# NXP_USB_Programmer.net
KiCad netlist of a schematic drawn in Altium Designer
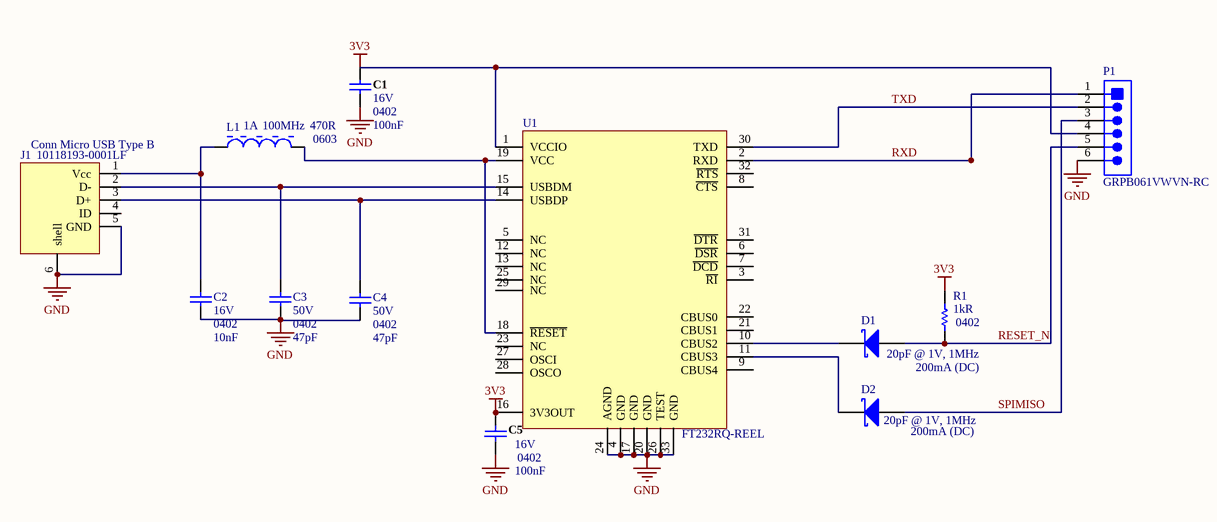
[diagram p0: NXP_USB_Programmer.SchDoc]

(export (version "E")
  (design (tool "Eeschema 10.0.6"))
  (components
    (comp (ref "C1")
      (value "CAP CER 0.1UF 16V X7R 0402")
      (footprint "PcbLib1:SM0402")
      (description "0.1µF ±10% 16V Ceramic Capacitor X7R 0402 (1005 Metric)")
      (fields
        (field (name "MANUFACTURER") "Yageo")
        (field (name "MANUFACTURER PART NUMBER") "CC0402KRX7R7BB104")
        (field (name "VOLTAGE RATING") "16V")
        (field (name "CASE/PACKAGE") "0402")
        (field (name "CAPACITANCE") "100nF")
      )
      (libsource (lib "") (part "CC0402KRX7R7BB104_1"))
    )
    (comp (ref "C2")
      (value "CAP CER 10000PF 16V X7R 0402")
      (footprint "PcbLib1:SM0402")
      (description "10000pF ±10% 16V Ceramic Capacitor X7R 0402 (1005 Metric)")
      (fields
        (field (name "TOLERANCE") "Â±10%")
        (field (name "MANUFACTURER") "KEMET")
        (field (name "VOLTAGE RATING") "16V")
        (field (name "CASE/PACKAGE") "0402")
        (field (name "CAPACITANCE") "10nF")
      )
      (libsource (lib "Schlib1") (part "C0402C103K4RALTU"))
    )
    (comp (ref "C3")
      (value "CAP CER 47PF 50V NP0 0402")
      (footprint "PcbLib1:SM0402")
      (description "47pF ±0.5pF 50V Ceramic Capacitor C0G, NP0 0402 (1005 Metric)")
      (fields
        (field (name "MANUFACTURER") "KEMET")
        (field (name "MANUFACTURER PART NUMBER") "C0402C470D5GACTU")
        (field (name "VOLTAGE RATING") "50V")
        (field (name "CASE/PACKAGE") "0402")
        (field (name "CAPACITANCE") "47pF")
      )
      (libsource (lib "Schlib1") (part "C0402C470D5GACTU"))
    )
    (comp (ref "C4")
      (value "CAP CER 47PF 50V NP0 0402")
      (footprint "PcbLib1:SM0402")
      (description "47pF ±0.5pF 50V Ceramic Capacitor C0G, NP0 0402 (1005 Metric)")
      (fields
        (field (name "MANUFACTURER") "KEMET")
        (field (name "MANUFACTURER PART NUMBER") "C0402C470D5GACTU")
        (field (name "VOLTAGE RATING") "50V")
        (field (name "CASE/PACKAGE") "0402")
        (field (name "CAPACITANCE") "47pF")
      )
      (libsource (lib "Schlib1") (part "C0402C470D5GACTU"))
    )
    (comp (ref "C5")
      (value "CAP CER 0.1UF 16V X7R 0402")
      (footprint "PcbLib1:SM0402")
      (description "0.1µF ±10% 16V Ceramic Capacitor X7R 0402 (1005 Metric)")
      (fields
        (field (name "MANUFACTURER") "Yageo")
        (field (name "MANUFACTURER PART NUMBER") "CC0402KRX7R7BB104")
        (field (name "VOLTAGE RATING") "16V")
        (field (name "CASE/PACKAGE") "0402")
        (field (name "CAPACITANCE") "100nF")
      )
      (libsource (lib "Schlib1") (part "CC0402KRX7R7BB104"))
    )
    (comp (ref "D1")
      (value "DIODE SCHOTTKY 30V 200MA SOD523")
      (footprint "PcbLib1:DIODE SOD523")
      (description "Schottky Barrier Diode, 30 V, 0.2 A, -55 to 125 degC, 2-Pin SOD523F, RoHS, Tape and Reel")
      (fields
        (field (name "MANUFACTURER PART NUMBER") "RB521S30,115")
        (field (name "MANUFACTURER") "Nexperia")
        (field (name "CAPACITANCE @ VR, F") "20pF @ 1V, 1MHz")
        (field (name "CURRENT - AVERAGE RECTIFIED (IO)") "200mA (DC)")
      )
      (libsource (lib "Schlib1") (part "RB521S30,115"))
    )
    (comp (ref "D2")
      (value "DIODE SCHOTTKY 30V 200MA SOD523")
      (footprint "PcbLib1:DIODE SOD523")
      (description "Schottky Barrier Diode, 30 V, 0.2 A, -55 to 125 degC, 2-Pin SOD523F, RoHS, Tape and Reel")
      (fields
        (field (name "MANUFACTURER PART NUMBER") "RB521S30,115")
        (field (name "MANUFACTURER") "Nexperia")
        (field (name "CAPACITANCE @ VR, F") "20pF @ 1V, 1MHz")
        (field (name "CURRENT - AVERAGE RECTIFIED (IO)") "200mA (DC)")
      )
      (libsource (lib "Schlib1") (part "RB521S30,115"))
    )
    (comp (ref "J1")
      (value "10118193-0001LF")
      (footprint "PcbLib1:FCI-10118193-0001LF-5_V")
      (description "USB - micro B USB 2.0 Receptacle Connector 5 Position Surface Mount, Right Angle; Through Hole")
      (fields
        (field (name "MANUFACTURER") "Amphenol ICC")
        (field (name "DESCRIPTION2") "Conn Micro USB Type B")
        (field (name "MANUFACTURER PART NUMBER") "10118193-0001LF")
      )
      (libsource (lib "Schlib1") (part "10118193-0001LF"))
    )
    (comp (ref "L1")
      (value "FERRITE BEAD 470 OHM 0603 1LN")
      (footprint "PcbLib1:BLM18PG471SN1D")
      (description "470 Ohms @ 100MHz 1 Power Line Ferrite Bead 0603 (1608 Metric) 1A 200mOhm")
      (fields
        (field (name "MANUFACTURER") "Murata")
        (field (name "MANUFACTURER PART NUMBER") "BLM18PG471SN1D")
        (field (name "MAX CURRENT RATING") "1A")
        (field (name "TEST FREQUENCY") "100MHz")
        (field (name "IMPEDANCE") "470R")
        (field (name "CASE/PACKAGE") "0603")
      )
      (libsource (lib "Schlib1") (part "BLM18PG471SN1D"))
    )
    (comp (ref "P1")
      (value "CONN HEADER VERT 6POS 1.27MM")
      (footprint "PcbLib1:SLIN-GRPB061VWVN-RC_V")
      (description "Connector Header Through Hole 6 position 0.050\" (1.27mm)")
      (fields
        (field (name "MANUFACTURER") "Sullins")
        (field (name "MANUFACTURER PART NUMBER") "GRPB061VWVN-RC")
      )
      (libsource (lib "Schlib1") (part "GRPB061VWVN-RC"))
    )
    (comp (ref "R1")
      (value "RES 1K OHM 0.5% 1/16W 0402")
      (footprint "PcbLib1:SM0402")
      (description "1 kOhms ±0.5% 0.063W, 1/16W Chip Resistor 0402 (1005 Metric) Automotive AEC-Q200 Thin Film")
      (fields
        (field (name "TOLERANCE") "1 %")
        (field (name "POWER") "0.063 W")
        (field (name "RESISTANCE") "1kR")
        (field (name "CASE/PACKAGE") "0402")
      )
      (libsource (lib "Schlib1") (part "RNCF0402DTE1K00"))
    )
    (comp (ref "U1")
      (value "FT232RQ-REEL")
      (footprint "PcbLib1:COM-UART-FT232R-SQ32")
      (description "USB Bridge, USB to UART USB 2.0 UART Interface 32-QFN (5x5)")
      (fields (field (name "MANUFACTURER") "FTDI") (field (name "MANUFACTURER PART NUMBER") "FT232RQ-REEL"))
      (libsource (lib "Schlib1") (part "COM-UART-FT232R-SQ32"))
    )
  )
  (nets
    (net (code "1") (name "/RESET_N") (class "Default")
      (node (ref "D1") (pin "1") (pinfunction "A_1") (pintype "passive"))
      (node (ref "P1") (pin "5") (pinfunction "5_5") (pintype "passive"))
      (node (ref "R1") (pin "1") (pinfunction "1_1") (pintype "passive"))
    )
    (net (code "2") (name "/RXD") (class "Default")
      (node (ref "P1") (pin "1") (pinfunction "1_1") (pintype "passive"))
      (node (ref "U1") (pin "2") (pinfunction "RXD_2") (pintype "passive"))
    )
    (net (code "3") (name "/SPIMISO") (class "Default")
      (node (ref "D2") (pin "1") (pinfunction "A_1") (pintype "passive"))
      (node (ref "P1") (pin "3") (pinfunction "3_3") (pintype "passive"))
    )
    (net (code "4") (name "/TXD") (class "Default")
      (node (ref "P1") (pin "2") (pinfunction "2_2") (pintype "passive"))
      (node (ref "U1") (pin "30") (pinfunction "TXD_30") (pintype "passive"))
    )
    (net (code "5") (name "3V3") (class "Default")
      (node (ref "C1") (pin "2") (pinfunction "2_2") (pintype "passive"))
      (node (ref "C5") (pin "2") (pinfunction "2_2") (pintype "passive"))
      (node (ref "P1") (pin "4") (pinfunction "4_4") (pintype "passive"))
      (node (ref "R1") (pin "2") (pinfunction "2_2") (pintype "passive"))
      (node (ref "U1") (pin "1") (pinfunction "VCCIO_1") (pintype "passive"))
      (node (ref "U1") (pin "16") (pinfunction "3V3OUT_16") (pintype "passive"))
    )
    (net (code "6") (name "GND") (class "Default")
      (node (ref "C1") (pin "1") (pinfunction "1_1") (pintype "passive"))
      (node (ref "C2") (pin "1") (pinfunction "1_1") (pintype "passive"))
      (node (ref "C3") (pin "1") (pinfunction "1_1") (pintype "passive"))
      (node (ref "C4") (pin "1") (pinfunction "1_1") (pintype "passive"))
      (node (ref "C5") (pin "1") (pinfunction "1_1") (pintype "passive"))
      (node (ref "J1") (pin "5") (pinfunction "GND_5") (pintype "passive"))
      (node (ref "J1") (pin "6") (pinfunction "shell_6") (pintype "passive"))
      (node (ref "P1") (pin "6") (pinfunction "6_6") (pintype "passive"))
      (node (ref "U1") (pin "17") (pinfunction "GND_17") (pintype "passive"))
      (node (ref "U1") (pin "20") (pinfunction "GND_20") (pintype "passive"))
      (node (ref "U1") (pin "24") (pinfunction "AGND_24") (pintype "passive"))
      (node (ref "U1") (pin "26") (pinfunction "TEST_26") (pintype "passive"))
      (node (ref "U1") (pin "33") (pinfunction "GND_33") (pintype "passive"))
      (node (ref "U1") (pin "4") (pinfunction "GND_4") (pintype "passive"))
    )
    (net (code "7") (name "Net-(D1-K)") (class "Default")
      (node (ref "D1") (pin "2") (pinfunction "K_2") (pintype "passive"))
      (node (ref "U1") (pin "10") (pinfunction "CBUS2_10") (pintype "passive"))
    )
    (net (code "8") (name "Net-(D2-K)") (class "Default")
      (node (ref "D2") (pin "2") (pinfunction "K_2") (pintype "passive"))
      (node (ref "U1") (pin "11") (pinfunction "CBUS3_11") (pintype "passive"))
    )
    (net (code "9") (name "Net-(J1-D+)") (class "Default")
      (node (ref "C4") (pin "2") (pinfunction "2_2") (pintype "passive"))
      (node (ref "J1") (pin "3") (pinfunction "D+_3") (pintype "passive"))
      (node (ref "U1") (pin "14") (pinfunction "USBDP_14") (pintype "passive"))
    )
    (net (code "10") (name "Net-(J1-D-)") (class "Default")
      (node (ref "C3") (pin "2") (pinfunction "2_2") (pintype "passive"))
      (node (ref "J1") (pin "2") (pinfunction "D-_2") (pintype "passive"))
      (node (ref "U1") (pin "15") (pinfunction "USBDM_15") (pintype "passive"))
    )
    (net (code "11") (name "Net-(J1-Vcc)") (class "Default")
      (node (ref "C2") (pin "2") (pinfunction "2_2") (pintype "passive"))
      (node (ref "J1") (pin "1") (pinfunction "Vcc_1") (pintype "passive"))
      (node (ref "L1") (pin "1") (pinfunction "1_1") (pintype "passive"))
    )
    (net (code "12") (name "Net-(U1-VCC)") (class "Default")
      (node (ref "L1") (pin "2") (pinfunction "2_2") (pintype "passive"))
      (node (ref "U1") (pin "18") (pinfunction "~{RESET}_18") (pintype "passive"))
      (node (ref "U1") (pin "19") (pinfunction "VCC_19") (pintype "passive"))
    )
    (net (code "13") (name "unconnected-(J1-ID-Pad4)") (class "Default")
      (node (ref "J1") (pin "4") (pinfunction "ID_4") (pintype "passive"))
    )
    (net (code "14") (name "unconnected-(U1-CBUS0-Pad22)") (class "Default")
      (node (ref "U1") (pin "22") (pinfunction "CBUS0_22") (pintype "passive"))
    )
    (net (code "15") (name "unconnected-(U1-CBUS1-Pad21)") (class "Default")
      (node (ref "U1") (pin "21") (pinfunction "CBUS1_21") (pintype "passive"))
    )
    (net (code "16") (name "unconnected-(U1-CBUS4-Pad9)") (class "Default")
      (node (ref "U1") (pin "9") (pinfunction "CBUS4_9") (pintype "passive"))
    )
    (net (code "17") (name "unconnected-(U1-NC-Pad5)") (class "Default")
      (node (ref "U1") (pin "5") (pinfunction "NC_5") (pintype "passive"))
    )
    (net (code "18") (name "unconnected-(U1-NC-Pad12)") (class "Default")
      (node (ref "U1") (pin "12") (pinfunction "NC_12") (pintype "passive"))
    )
    (net (code "19") (name "unconnected-(U1-NC-Pad13)") (class "Default")
      (node (ref "U1") (pin "13") (pinfunction "NC_13") (pintype "passive"))
    )
    (net (code "20") (name "unconnected-(U1-NC-Pad23)") (class "Default")
      (node (ref "U1") (pin "23") (pinfunction "NC_23") (pintype "passive"))
    )
    (net (code "21") (name "unconnected-(U1-NC-Pad25)") (class "Default")
      (node (ref "U1") (pin "25") (pinfunction "NC_25") (pintype "passive"))
    )
    (net (code "22") (name "unconnected-(U1-NC-Pad29)") (class "Default")
      (node (ref "U1") (pin "29") (pinfunction "NC_29") (pintype "passive"))
    )
    (net (code "23") (name "unconnected-(U1-OSCI-Pad27)") (class "Default")
      (node (ref "U1") (pin "27") (pinfunction "OSCI_27") (pintype "passive"))
    )
    (net (code "24") (name "unconnected-(U1-OSCO-Pad28)") (class "Default")
      (node (ref "U1") (pin "28") (pinfunction "OSCO_28") (pintype "passive"))
    )
    (net (code "25") (name "unconnected-(U1-~{CTS}-Pad8)") (class "Default")
      (node (ref "U1") (pin "8") (pinfunction "~{CTS}_8") (pintype "passive"))
    )
    (net (code "26") (name "unconnected-(U1-~{DCD}-Pad7)") (class "Default")
      (node (ref "U1") (pin "7") (pinfunction "~{DCD}_7") (pintype "passive"))
    )
    (net (code "27") (name "unconnected-(U1-~{DSR}-Pad6)") (class "Default")
      (node (ref "U1") (pin "6") (pinfunction "~{DSR}_6") (pintype "passive"))
    )
    (net (code "28") (name "unconnected-(U1-~{DTR}-Pad31)") (class "Default")
      (node (ref "U1") (pin "31") (pinfunction "~{DTR}_31") (pintype "passive"))
    )
    (net (code "29") (name "unconnected-(U1-~{RI}-Pad3)") (class "Default")
      (node (ref "U1") (pin "3") (pinfunction "~{RI}_3") (pintype "passive"))
    )
    (net (code "30") (name "unconnected-(U1-~{RTS}-Pad32)") (class "Default")
      (node (ref "U1") (pin "32") (pinfunction "~{RTS}_32") (pintype "passive"))
    )
  )
)
